# motor_driver.net
KiCad netlist of a schematic drawn in Altium Designer
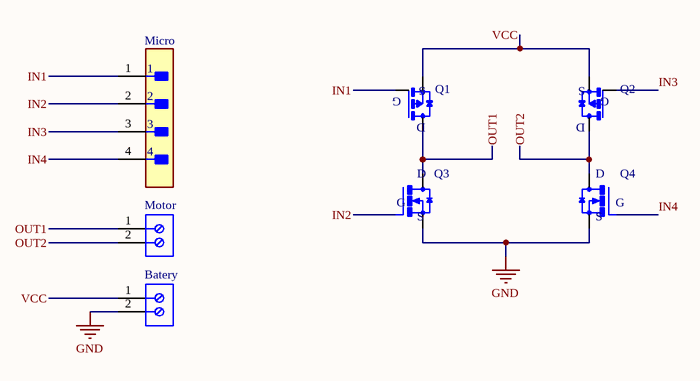
[diagram p0: motor driver.SchDoc]

(export (version "E")
  (design (tool "Eeschema 10.0.6"))
  (components
    (comp (ref "Batery")
      (value "282836-2")
      (footprint "TECO-282836-2_V")
      (description "Female Header, Pitch 5 mm, 1 x 2 Position, Height 10 mm, Tail Length 3.5 mm, Rohs, Bulk")
      (fields (field (name "VOLTAGE") "300V") (field (name "MANUFACTURER") "TE Connectivity"))
      (libsource (lib "terminals block 2h") (part "CMP-1684-00017-1"))
    )
    (comp (ref "Micro")
      (value "M20-9990445")
      (footprint "FP-M20-9990445-MFG")
      (description "M20-9990445 Conn Unshrouded Header HDR 4 POS 2.54mm Solder ST Thru-Hole Bulk/Loose")
      (libsource (lib "male data header 4h") (part "CMP-00671-05399696-1"))
    )
    (comp (ref "Motor")
      (value "282836-2")
      (footprint "TECO-282836-2_V")
      (description "Female Header, Pitch 5 mm, 1 x 2 Position, Height 10 mm, Tail Length 3.5 mm, Rohs, Bulk")
      (fields (field (name "VOLTAGE") "300V") (field (name "MANUFACTURER") "TE Connectivity"))
      (libsource (lib "terminals block 2h") (part "CMP-1684-00017-1"))
    )
    (comp (ref "Q1")
      (value "AO3401A")
      (footprint "SOT23")
      (description "P-Channel 30V 4A (Ta) 1.4W (Ta) Surface Mount SOT-23-3L")
      (fields (field (name "MF") "Alpha &"))
      (libsource (lib "AO3401A") (part "AO3401A"))
    )
    (comp (ref "Q2")
      (value "AO3401A")
      (footprint "SOT23")
      (description "P-Channel 30V 4A (Ta) 1.4W (Ta) Surface Mount SOT-23-3L")
      (fields (field (name "MF") "Alpha &"))
      (libsource (lib "") (part "AO3401A_1"))
    )
    (comp (ref "Q3")
      (value "IRLML6344TRPBF")
      (footprint "SOT23")
      (description "N-Channel 30V 5A (Ta) 1.3W (Ta) Surface Mount Micro3â„¢/SOT-23")
      (fields (field (name "MF") "Infineon Technologies"))
      (libsource (lib "") (part "IRLML6344TRPBF_1"))
    )
    (comp (ref "Q4")
      (value "IRLML6344TRPBF")
      (footprint "SOT23")
      (description "N-Channel 30V 5A (Ta) 1.3W (Ta) Surface Mount Micro3â„¢/SOT-23")
      (fields (field (name "MF") "Infineon Technologies"))
      (libsource (lib "IRLML6344TRPBF c chanel Symbol") (part "IRLML6344TRPBF"))
    )
  )
  (nets
    (net (code "1") (name "/IN1") (class "Default")
      (node (ref "Micro") (pin "1") (pinfunction "1_1") (pintype "passive"))
      (node (ref "Q1") (pin "1") (pinfunction "G_1") (pintype "passive"))
    )
    (net (code "2") (name "/IN2") (class "Default")
      (node (ref "Micro") (pin "2") (pinfunction "2_2") (pintype "passive"))
      (node (ref "Q3") (pin "1") (pinfunction "G_1") (pintype "passive"))
    )
    (net (code "3") (name "/IN3") (class "Default")
      (node (ref "Micro") (pin "3") (pinfunction "3_3") (pintype "passive"))
      (node (ref "Q2") (pin "1") (pinfunction "G_1") (pintype "passive"))
    )
    (net (code "4") (name "/IN4") (class "Default")
      (node (ref "Micro") (pin "4") (pinfunction "4_4") (pintype "passive"))
      (node (ref "Q4") (pin "1") (pinfunction "G_1") (pintype "passive"))
    )
    (net (code "5") (name "/OUT1") (class "Default")
      (node (ref "Motor") (pin "1") (pinfunction "1_1") (pintype "passive"))
      (node (ref "Q1") (pin "3") (pinfunction "D_3") (pintype "passive"))
      (node (ref "Q3") (pin "3") (pinfunction "D_3") (pintype "passive"))
    )
    (net (code "6") (name "/OUT2") (class "Default")
      (node (ref "Motor") (pin "2") (pinfunction "2_2") (pintype "passive"))
      (node (ref "Q2") (pin "3") (pinfunction "D_3") (pintype "passive"))
      (node (ref "Q4") (pin "3") (pinfunction "D_3") (pintype "passive"))
    )
    (net (code "7") (name "/VCC") (class "Default")
      (node (ref "Batery") (pin "1") (pinfunction "1_1") (pintype "passive"))
      (node (ref "Q1") (pin "2") (pinfunction "S_2") (pintype "passive"))
      (node (ref "Q2") (pin "2") (pinfunction "S_2") (pintype "passive"))
    )
    (net (code "8") (name "GND") (class "Default")
      (node (ref "Batery") (pin "2") (pinfunction "2_2") (pintype "passive"))
      (node (ref "Q3") (pin "2") (pinfunction "S_2") (pintype "passive"))
      (node (ref "Q4") (pin "2") (pinfunction "S_2") (pintype "passive"))
    )
  )
)
